# cSLIM_FRAM.net
KiCad netlist of a schematic drawn in Altium Designer
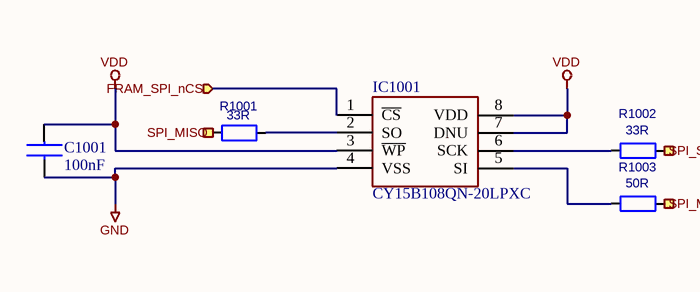
[diagram p0: cSLIM_FRAM.SchDoc]

(export (version "E")
  (design (tool "Eeschema 10.0.6"))
  (components
    (comp (ref "C1001")
      (value "100nF")
      (footprint "cSLIM-SA:CAPC1608X90N")
      (description "Capacitor")
      (fields
        (field (name "MANUFACTURER_PART_NUMBER") "06033G104ZAT2A")
        (field (name "MOUSER PART NUMBER") "581-06033G104Z")
      )
      (libsource (lib "cSLIM-SA") (part "C"))
    )
    (comp (ref "IC1001")
      (value "CY15B108QN-20LPXC")
      (footprint "cSLIM-SA:SON65P323X328X55-8N")
      (description "Integrated Circuit")
      (fields (field (name "MOUSER PART NUMBER") "727-CY15B108QN20LPXC"))
      (libsource (lib "cSLIM-SA") (part "CY15B108QN-20LPXC"))
    )
    (comp (ref "R1001") (value "33R") (footprint "RESC1608X55N") (libsource (lib "") (part "R_1")))
    (comp (ref "R1002") (value "33R") (footprint "RESC1608X55N") (libsource (lib "cSLIM-SA") (part "R")))
    (comp (ref "R1003") (value "50R") (footprint "RESC1608X55N") (libsource (lib "cSLIM-SA") (part "R")))
  )
  (nets
    (net (code "1") (name "/FRAM_SPI_nCS") (class "Default")
      (node (ref "IC1001") (pin "1") (pinfunction "~{CS}_1") (pintype "passive"))
    )
    (net (code "2") (name "/SPI_MISO") (class "Default")
      (node (ref "R1001") (pin "1") (pinfunction "1_1") (pintype "passive"))
    )
    (net (code "3") (name "/SPI_MOSI") (class "Default")
      (node (ref "R1003") (pin "1") (pinfunction "1_1") (pintype "passive"))
    )
    (net (code "4") (name "/SPI_SCK") (class "Default")
      (node (ref "R1002") (pin "1") (pinfunction "1_1") (pintype "passive"))
    )
    (net (code "5") (name "GND") (class "Default")
      (node (ref "C1001") (pin "2") (pinfunction "2_2") (pintype "passive"))
      (node (ref "IC1001") (pin "4") (pinfunction "VSS_4") (pintype "passive"))
    )
    (net (code "6") (name "Net-(IC1001-SCK)") (class "Default")
      (node (ref "IC1001") (pin "6") (pinfunction "SCK_6") (pintype "passive"))
      (node (ref "R1002") (pin "2") (pinfunction "2_2") (pintype "passive"))
    )
    (net (code "7") (name "Net-(IC1001-SI)") (class "Default")
      (node (ref "IC1001") (pin "5") (pinfunction "SI_5") (pintype "passive"))
      (node (ref "R1003") (pin "2") (pinfunction "2_2") (pintype "passive"))
    )
    (net (code "8") (name "Net-(IC1001-SO)") (class "Default")
      (node (ref "IC1001") (pin "2") (pinfunction "SO_2") (pintype "passive"))
      (node (ref "R1001") (pin "2") (pinfunction "2_2") (pintype "passive"))
    )
    (net (code "9") (name "VDD") (class "Default")
      (node (ref "C1001") (pin "1") (pinfunction "1_1") (pintype "passive"))
      (node (ref "IC1001") (pin "3") (pinfunction "~{WP}_3") (pintype "passive"))
      (node (ref "IC1001") (pin "7") (pinfunction "DNU_7") (pintype "passive"))
      (node (ref "IC1001") (pin "8") (pinfunction "VDD_8") (pintype "passive"))
    )
  )
)
